# main_connector.net
KiCad netlist of a schematic drawn in Altium Designer
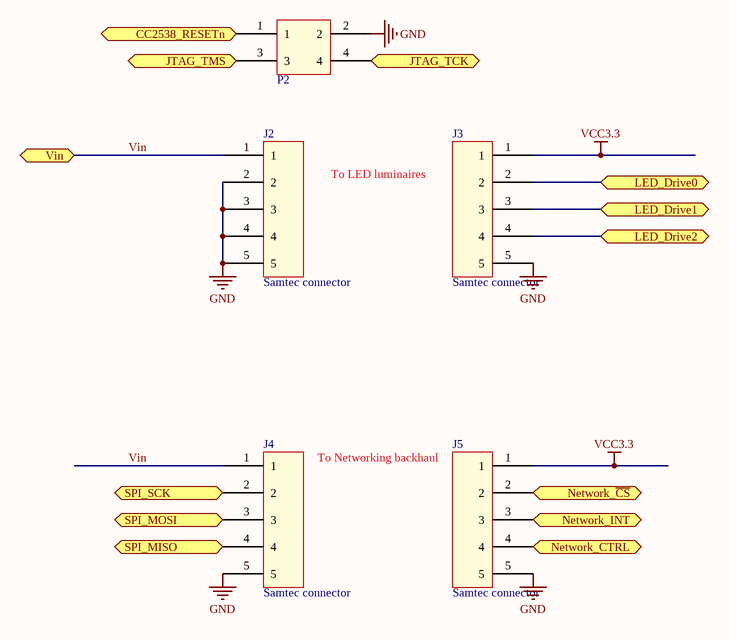
[diagram p0: main_connector.SchDoc]

(export (version "E")
  (design (tool "Eeschema 10.0.6"))
  (components
    (comp (ref "J2")
      (value "Samtec connector")
      (footprint "SFM-105-02-L-S")
      (description "Samtec connector, 1.27 mm, single row, 5 pos SMD")
      (libsource (lib "") (part "Samtec conntector_1"))
    )
    (comp (ref "J3")
      (value "Samtec connector")
      (footprint "SFM-105-02-L-S")
      (description "Samtec connector, 1.27 mm, single row, 5 pos SMD")
      (libsource (lib "connectors") (part "Samtec conntector"))
    )
    (comp (ref "J4")
      (value "Samtec connector")
      (footprint "SFM-105-02-L-S")
      (description "Samtec connector, 1.27 mm, single row, 5 pos SMD")
      (libsource (lib "") (part "Samtec conntector_1"))
    )
    (comp (ref "J5")
      (value "Samtec connector")
      (footprint "SFM-105-02-L-S")
      (description "Samtec connector, 1.27 mm, single row, 5 pos SMD")
      (libsource (lib "connectors") (part "Samtec conntector"))
    )
    (comp (ref "P2")
      (value "2 x 2 header SMD")
      (footprint "2x2 header SMD")
      (description "2x2 100 mil header SMD")
      (libsource (lib "connectors") (part "2 x 2 header SMD"))
    )
  )
  (nets
    (net (code "1") (name "/CC2538_RESETn") (class "Default")
      (node (ref "P2") (pin "1") (pinfunction "1_1") (pintype "passive"))
    )
    (net (code "2") (name "/JTAG_TCK") (class "Default")
      (node (ref "P2") (pin "4") (pinfunction "4_4") (pintype "passive"))
    )
    (net (code "3") (name "/JTAG_TMS") (class "Default")
      (node (ref "P2") (pin "3") (pinfunction "3_3") (pintype "passive"))
    )
    (net (code "4") (name "/LED_Drive0") (class "Default")
      (node (ref "J3") (pin "2") (pinfunction "2_2") (pintype "passive"))
    )
    (net (code "5") (name "/LED_Drive1") (class "Default")
      (node (ref "J3") (pin "3") (pinfunction "3_3") (pintype "passive"))
    )
    (net (code "6") (name "/LED_Drive2") (class "Default")
      (node (ref "J3") (pin "4") (pinfunction "4_4") (pintype "passive"))
    )
    (net (code "7") (name "/Network_CTRL") (class "Default")
      (node (ref "J5") (pin "4") (pinfunction "4_4") (pintype "passive"))
    )
    (net (code "8") (name "/Network_INT") (class "Default")
      (node (ref "J5") (pin "3") (pinfunction "3_3") (pintype "passive"))
    )
    (net (code "9") (name "/Network_~{CS}") (class "Default")
      (node (ref "J5") (pin "2") (pinfunction "2_2") (pintype "passive"))
    )
    (net (code "10") (name "/SPI_MISO") (class "Default")
      (node (ref "J4") (pin "4") (pinfunction "4_4") (pintype "passive"))
    )
    (net (code "11") (name "/SPI_MOSI") (class "Default")
      (node (ref "J4") (pin "3") (pinfunction "3_3") (pintype "passive"))
    )
    (net (code "12") (name "/SPI_SCK") (class "Default")
      (node (ref "J4") (pin "2") (pinfunction "2_2") (pintype "passive"))
    )
    (net (code "13") (name "/Vin") (class "Default")
      (node (ref "J2") (pin "1") (pinfunction "1_1") (pintype "passive"))
      (node (ref "J4") (pin "1") (pinfunction "1_1") (pintype "passive"))
    )
    (net (code "14") (name "GND") (class "Default")
      (node (ref "J2") (pin "2") (pinfunction "2_2") (pintype "passive"))
      (node (ref "J2") (pin "3") (pinfunction "3_3") (pintype "passive"))
      (node (ref "J2") (pin "4") (pinfunction "4_4") (pintype "passive"))
      (node (ref "J2") (pin "5") (pinfunction "5_5") (pintype "passive"))
      (node (ref "J3") (pin "5") (pinfunction "5_5") (pintype "passive"))
      (node (ref "J4") (pin "5") (pinfunction "5_5") (pintype "passive"))
      (node (ref "J5") (pin "5") (pinfunction "5_5") (pintype "passive"))
      (node (ref "P2") (pin "2") (pinfunction "2_2") (pintype "passive"))
    )
    (net (code "15") (name "VCC3.3") (class "Default")
      (node (ref "J3") (pin "1") (pinfunction "1_1") (pintype "passive"))
      (node (ref "J5") (pin "1") (pinfunction "1_1") (pintype "passive"))
    )
  )
)
